# Wiegand_RS485.net
KiCad netlist of a schematic drawn in EAGLE
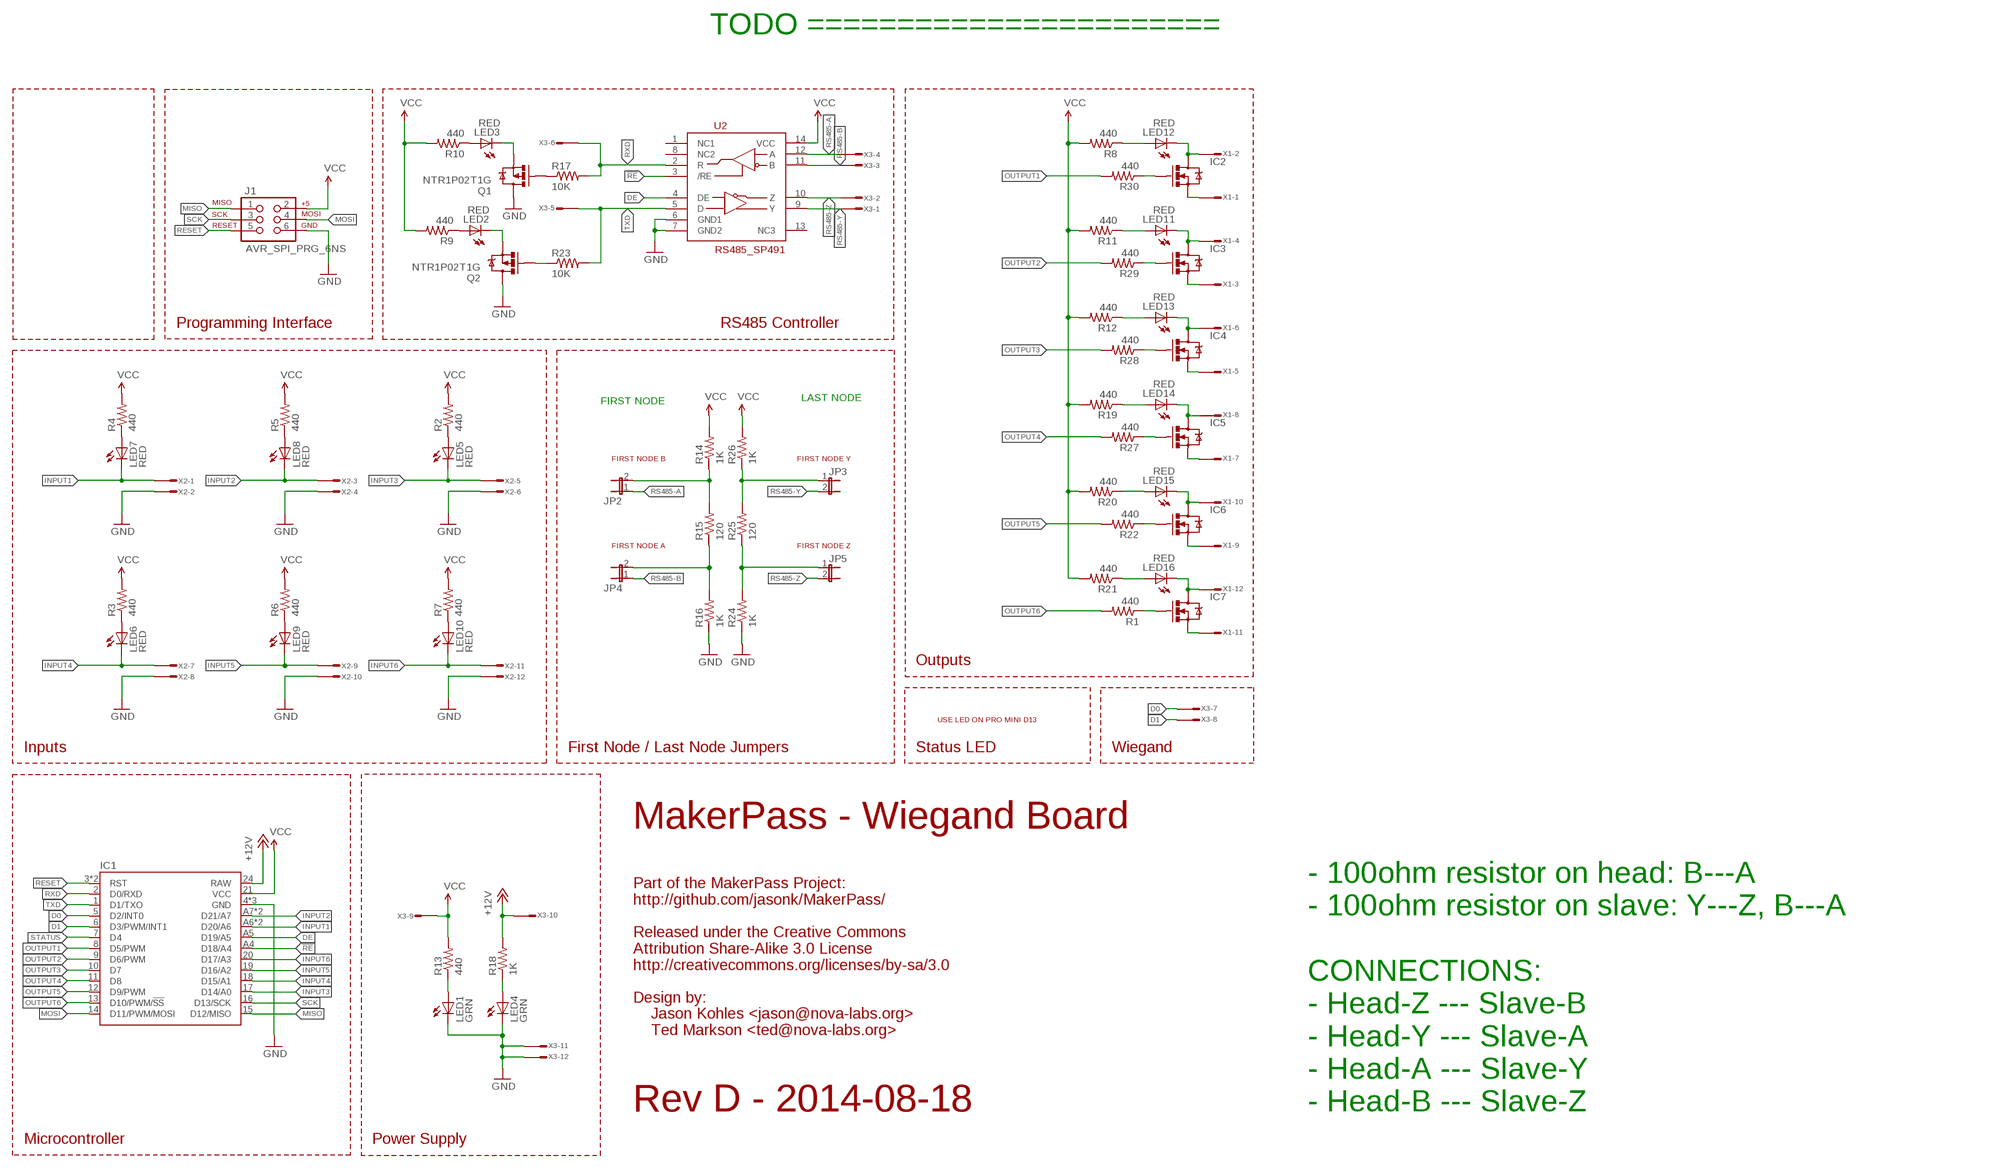
[diagram p0: schematic, sheet 1]

(export (version "E")
  (design (tool "Eeschema 10.0.6"))
  (components
    (comp (ref "IC1")
      (value "ARDUINO-PRO-MINI-ALIEXPRESS")
      (footprint "eagle-import:ARDUINO-PRO-MINI-ALIEXPRESS")
      (libsource (lib "eagle-import") (part "ARDUINO-PRO-MINI-ALIEXPRESS"))
    )
    (comp (ref "IC2")
      (value "MOSFET-NCHANNEL-SOT23")
      (footprint "eagle-import:SOT23")
      (fields (field (name "MFG") "DIODES INC"))
      (libsource (lib "eagle-import") (part "MOSFET-NCHANNEL-SOT23"))
    )
    (comp (ref "IC3")
      (value "MOSFET-NCHANNEL-SOT23")
      (footprint "eagle-import:SOT23")
      (fields (field (name "MFG") "DIODES INC"))
      (libsource (lib "eagle-import") (part "MOSFET-NCHANNEL-SOT23"))
    )
    (comp (ref "IC4")
      (value "MOSFET-NCHANNEL-SOT23")
      (footprint "eagle-import:SOT23")
      (fields (field (name "MFG") "DIODES INC"))
      (libsource (lib "eagle-import") (part "MOSFET-NCHANNEL-SOT23"))
    )
    (comp (ref "IC5")
      (value "MOSFET-NCHANNEL-SOT23")
      (footprint "eagle-import:SOT23")
      (fields (field (name "MFG") "DIODES INC"))
      (libsource (lib "eagle-import") (part "MOSFET-NCHANNEL-SOT23"))
    )
    (comp (ref "IC6")
      (value "MOSFET-NCHANNEL-SOT23")
      (footprint "eagle-import:SOT23")
      (fields (field (name "MFG") "DIODES INC"))
      (libsource (lib "eagle-import") (part "MOSFET-NCHANNEL-SOT23"))
    )
    (comp (ref "IC7")
      (value "MOSFET-NCHANNEL-SOT23")
      (footprint "eagle-import:SOT23")
      (fields (field (name "MFG") "DIODES INC"))
      (libsource (lib "eagle-import") (part "MOSFET-NCHANNEL-SOT23"))
    )
    (comp (ref "J1")
      (value "AVR_SPI_PRG_6NS")
      (footprint "eagle-import:2X3-NS")
      (libsource (lib "eagle-import") (part "AVR_SPI_PRG_6NS"))
    )
    (comp (ref "JP2")
      (value "JUMPER-2PTH")
      (footprint "eagle-import:1X02")
      (libsource (lib "eagle-import") (part "JUMPER-2PTH"))
    )
    (comp (ref "JP3")
      (value "JUMPER-2PTH")
      (footprint "eagle-import:1X02")
      (libsource (lib "eagle-import") (part "JUMPER-2PTH"))
    )
    (comp (ref "JP4")
      (value "JUMPER-2PTH")
      (footprint "eagle-import:1X02")
      (libsource (lib "eagle-import") (part "JUMPER-2PTH"))
    )
    (comp (ref "JP5")
      (value "JUMPER-2PTH")
      (footprint "eagle-import:1X02")
      (libsource (lib "eagle-import") (part "JUMPER-2PTH"))
    )
    (comp (ref "LED1")
      (value "GRN")
      (footprint "eagle-import:LED-805")
      (libsource (lib "eagle-import") (part "LED-0805"))
    )
    (comp (ref "LED2")
      (value "RED")
      (footprint "eagle-import:LED-805")
      (libsource (lib "eagle-import") (part "LED-0805"))
    )
    (comp (ref "LED3")
      (value "RED")
      (footprint "eagle-import:LED-805")
      (libsource (lib "eagle-import") (part "LED-0805"))
    )
    (comp (ref "LED4")
      (value "GRN")
      (footprint "eagle-import:LED-805")
      (libsource (lib "eagle-import") (part "LED-0805"))
    )
    (comp (ref "LED5")
      (value "RED")
      (footprint "eagle-import:LED-805")
      (libsource (lib "eagle-import") (part "LED-0805"))
    )
    (comp (ref "LED6")
      (value "RED")
      (footprint "eagle-import:LED-805")
      (libsource (lib "eagle-import") (part "LED-0805"))
    )
    (comp (ref "LED7")
      (value "RED")
      (footprint "eagle-import:LED-805")
      (libsource (lib "eagle-import") (part "LED-0805"))
    )
    (comp (ref "LED8")
      (value "RED")
      (footprint "eagle-import:LED-805")
      (libsource (lib "eagle-import") (part "LED-0805"))
    )
    (comp (ref "LED9")
      (value "RED")
      (footprint "eagle-import:LED-805")
      (libsource (lib "eagle-import") (part "LED-0805"))
    )
    (comp (ref "LED10")
      (value "RED")
      (footprint "eagle-import:LED-805")
      (libsource (lib "eagle-import") (part "LED-0805"))
    )
    (comp (ref "LED11")
      (value "RED")
      (footprint "eagle-import:LED-805")
      (libsource (lib "eagle-import") (part "LED-0805"))
    )
    (comp (ref "LED12")
      (value "RED")
      (footprint "eagle-import:LED-805")
      (libsource (lib "eagle-import") (part "LED-0805"))
    )
    (comp (ref "LED13")
      (value "RED")
      (footprint "eagle-import:LED-805")
      (libsource (lib "eagle-import") (part "LED-0805"))
    )
    (comp (ref "LED14")
      (value "RED")
      (footprint "eagle-import:LED-805")
      (libsource (lib "eagle-import") (part "LED-0805"))
    )
    (comp (ref "LED15")
      (value "RED")
      (footprint "eagle-import:LED-805")
      (libsource (lib "eagle-import") (part "LED-0805"))
    )
    (comp (ref "LED16")
      (value "RED")
      (footprint "eagle-import:LED-805")
      (libsource (lib "eagle-import") (part "LED-0805"))
    )
    (comp (ref "Q1")
      (value "NTR1P02T1G")
      (footprint "eagle-import:SOT23-3")
      (libsource (lib "eagle-import") (part "MOSFET-PCHANNELSMD"))
    )
    (comp (ref "Q2")
      (value "NTR1P02T1G")
      (footprint "eagle-import:SOT23-3")
      (libsource (lib "eagle-import") (part "MOSFET-PCHANNELSMD"))
    )
    (comp (ref "R1")
      (value "440")
      (footprint "eagle-import:0603-RES")
      (libsource (lib "eagle-import") (part "RESISTOR0603-RES"))
    )
    (comp (ref "R2")
      (value "440")
      (footprint "eagle-import:0603-RES")
      (libsource (lib "eagle-import") (part "RESISTOR0603-RES"))
    )
    (comp (ref "R3")
      (value "440")
      (footprint "eagle-import:0603-RES")
      (libsource (lib "eagle-import") (part "RESISTOR0603-RES"))
    )
    (comp (ref "R4")
      (value "440")
      (footprint "eagle-import:0603-RES")
      (libsource (lib "eagle-import") (part "RESISTOR0603-RES"))
    )
    (comp (ref "R5")
      (value "440")
      (footprint "eagle-import:0603-RES")
      (libsource (lib "eagle-import") (part "RESISTOR0603-RES"))
    )
    (comp (ref "R6")
      (value "440")
      (footprint "eagle-import:0603-RES")
      (libsource (lib "eagle-import") (part "RESISTOR0603-RES"))
    )
    (comp (ref "R7")
      (value "440")
      (footprint "eagle-import:0603-RES")
      (libsource (lib "eagle-import") (part "RESISTOR0603-RES"))
    )
    (comp (ref "R8")
      (value "440")
      (footprint "eagle-import:0603-RES")
      (libsource (lib "eagle-import") (part "RESISTOR0603-RES"))
    )
    (comp (ref "R9")
      (value "440")
      (footprint "eagle-import:0603-RES")
      (libsource (lib "eagle-import") (part "RESISTOR0603-RES"))
    )
    (comp (ref "R10")
      (value "440")
      (footprint "eagle-import:0603-RES")
      (libsource (lib "eagle-import") (part "RESISTOR0603-RES"))
    )
    (comp (ref "R11")
      (value "440")
      (footprint "eagle-import:0603-RES")
      (libsource (lib "eagle-import") (part "RESISTOR0603-RES"))
    )
    (comp (ref "R12")
      (value "440")
      (footprint "eagle-import:0603-RES")
      (libsource (lib "eagle-import") (part "RESISTOR0603-RES"))
    )
    (comp (ref "R13")
      (value "440")
      (footprint "eagle-import:0603-RES")
      (libsource (lib "eagle-import") (part "RESISTOR0603-RES"))
    )
    (comp (ref "R14")
      (value "1K")
      (footprint "eagle-import:0603-RES")
      (libsource (lib "eagle-import") (part "RESISTOR0603-RES"))
    )
    (comp (ref "R15")
      (value "120")
      (footprint "eagle-import:0603-RES")
      (libsource (lib "eagle-import") (part "RESISTOR0603-RES"))
    )
    (comp (ref "R16")
      (value "1K")
      (footprint "eagle-import:0603-RES")
      (libsource (lib "eagle-import") (part "RESISTOR0603-RES"))
    )
    (comp (ref "R17")
      (value "10K")
      (footprint "eagle-import:0603-RES")
      (libsource (lib "eagle-import") (part "RESISTOR0603-RES"))
    )
    (comp (ref "R18")
      (value "1K")
      (footprint "eagle-import:0603-RES")
      (libsource (lib "eagle-import") (part "RESISTOR0603-RES"))
    )
    (comp (ref "R19")
      (value "440")
      (footprint "eagle-import:0603-RES")
      (libsource (lib "eagle-import") (part "RESISTOR0603-RES"))
    )
    (comp (ref "R20")
      (value "440")
      (footprint "eagle-import:0603-RES")
      (libsource (lib "eagle-import") (part "RESISTOR0603-RES"))
    )
    (comp (ref "R21")
      (value "440")
      (footprint "eagle-import:0603-RES")
      (libsource (lib "eagle-import") (part "RESISTOR0603-RES"))
    )
    (comp (ref "R22")
      (value "440")
      (footprint "eagle-import:0603-RES")
      (libsource (lib "eagle-import") (part "RESISTOR0603-RES"))
    )
    (comp (ref "R23")
      (value "10K")
      (footprint "eagle-import:0603-RES")
      (libsource (lib "eagle-import") (part "RESISTOR0603-RES"))
    )
    (comp (ref "R24")
      (value "1K")
      (footprint "eagle-import:0603-RES")
      (libsource (lib "eagle-import") (part "RESISTOR0603-RES"))
    )
    (comp (ref "R25")
      (value "120")
      (footprint "eagle-import:0603-RES")
      (libsource (lib "eagle-import") (part "RESISTOR0603-RES"))
    )
    (comp (ref "R26")
      (value "1K")
      (footprint "eagle-import:0603-RES")
      (libsource (lib "eagle-import") (part "RESISTOR0603-RES"))
    )
    (comp (ref "R27")
      (value "440")
      (footprint "eagle-import:0603-RES")
      (libsource (lib "eagle-import") (part "RESISTOR0603-RES"))
    )
    (comp (ref "R28")
      (value "440")
      (footprint "eagle-import:0603-RES")
      (libsource (lib "eagle-import") (part "RESISTOR0603-RES"))
    )
    (comp (ref "R29")
      (value "440")
      (footprint "eagle-import:0603-RES")
      (libsource (lib "eagle-import") (part "RESISTOR0603-RES"))
    )
    (comp (ref "R30")
      (value "440")
      (footprint "eagle-import:0603-RES")
      (libsource (lib "eagle-import") (part "RESISTOR0603-RES"))
    )
    (comp (ref "U2")
      (value "RS485_SP491")
      (footprint "eagle-import:SOIC-14")
      (libsource (lib "eagle-import") (part "RS485_SP491"))
    )
    (comp (ref "X1")
      (value "CON-1X12-TERMBLOCK-3.5MM")
      (footprint "eagle-import:CON-1X12-TERMBLOCK-3.5MM")
      (libsource (lib "eagle-import") (part "CON-1X12-TERMBLOCK-3.5MM"))
    )
    (comp (ref "X2")
      (value "CON-1X12-TERMBLOCK-3.5MM")
      (footprint "eagle-import:CON-1X12-TERMBLOCK-3.5MM")
      (libsource (lib "eagle-import") (part "CON-1X12-TERMBLOCK-3.5MM"))
    )
    (comp (ref "X3")
      (value "CON-1X12-TERMBLOCK-3.5MM")
      (footprint "eagle-import:CON-1X12-TERMBLOCK-3.5MM")
      (libsource (lib "eagle-import") (part "CON-1X12-TERMBLOCK-3.5MM"))
    )
  )
  (nets
    (net (code "1") (name "+12V") (class "Default")
      (node (ref "IC1") (pin "24") (pinfunction "RAW_24") (pintype "power_in"))
      (node (ref "R18") (pin "2") (pinfunction "2_2") (pintype "passive"))
      (node (ref "X3") (pin "10") (pinfunction "S_10") (pintype "passive"))
    )
    (net (code "2") (name "/~{RE}") (class "Default")
      (node (ref "IC1") (pin "A4") (pinfunction "D18/A4_A4") (pintype "bidirectional"))
      (node (ref "U2") (pin "3") (pinfunction "/RE_3") (pintype "bidirectional"))
    )
    (net (code "3") (name "D0") (class "Default")
      (node (ref "IC1") (pin "5") (pinfunction "D2/INT0_5") (pintype "bidirectional"))
      (node (ref "X3") (pin "7") (pinfunction "S_7") (pintype "passive"))
    )
    (net (code "4") (name "D1") (class "Default")
      (node (ref "IC1") (pin "6") (pinfunction "D3/PWM/INT1_6") (pintype "bidirectional"))
      (node (ref "X3") (pin "8") (pinfunction "S_8") (pintype "passive"))
    )
    (net (code "5") (name "DE") (class "Default")
      (node (ref "IC1") (pin "A5") (pinfunction "D19/A5_A5") (pintype "bidirectional"))
      (node (ref "U2") (pin "4") (pinfunction "DE_4") (pintype "bidirectional"))
    )
    (net (code "6") (name "GND") (class "Default")
      (node (ref "IC1") (pin "23") (pinfunction "GND_23") (pintype "power_in"))
      (node (ref "IC1") (pin "25") (pinfunction "GND_25") (pintype "power_in"))
      (node (ref "IC1") (pin "4") (pinfunction "GND_4") (pintype "power_in"))
      (node (ref "J1") (pin "6") (pinfunction "6_6") (pintype "passive"))
      (node (ref "LED1") (pin "C") (pinfunction "C_C") (pintype "passive"))
      (node (ref "LED4") (pin "C") (pinfunction "C_C") (pintype "passive"))
      (node (ref "Q1") (pin "3") (pinfunction "D_3") (pintype "passive"))
      (node (ref "Q2") (pin "3") (pinfunction "D_3") (pintype "passive"))
      (node (ref "R16") (pin "1") (pinfunction "1_1") (pintype "passive"))
      (node (ref "R24") (pin "1") (pinfunction "1_1") (pintype "passive"))
      (node (ref "U2") (pin "6") (pinfunction "GND1_6") (pintype "bidirectional"))
      (node (ref "U2") (pin "7") (pinfunction "GND2_7") (pintype "bidirectional"))
      (node (ref "X2") (pin "10") (pinfunction "S_10") (pintype "passive"))
      (node (ref "X2") (pin "12") (pinfunction "S_12") (pintype "passive"))
      (node (ref "X2") (pin "2") (pinfunction "S_2") (pintype "passive"))
      (node (ref "X2") (pin "4") (pinfunction "S_4") (pintype "passive"))
      (node (ref "X2") (pin "6") (pinfunction "S_6") (pintype "passive"))
      (node (ref "X2") (pin "8") (pinfunction "S_8") (pintype "passive"))
      (node (ref "X3") (pin "11") (pinfunction "S_11") (pintype "passive"))
      (node (ref "X3") (pin "12") (pinfunction "S_12") (pintype "passive"))
    )
    (net (code "7") (name "INPUT1") (class "Default")
      (node (ref "IC1") (pin "A6") (pinfunction "D20/A6_A6") (pintype "bidirectional"))
      (node (ref "IC1") (pin "A6@2") (pinfunction "D20/A6_A6@2") (pintype "bidirectional"))
      (node (ref "LED7") (pin "C") (pinfunction "C_C") (pintype "passive"))
      (node (ref "X2") (pin "1") (pinfunction "S_1") (pintype "passive"))
    )
    (net (code "8") (name "INPUT2") (class "Default")
      (node (ref "IC1") (pin "A7") (pinfunction "D21/A7_A7") (pintype "bidirectional"))
      (node (ref "IC1") (pin "A7@2") (pinfunction "D21/A7_A7@2") (pintype "bidirectional"))
      (node (ref "LED8") (pin "C") (pinfunction "C_C") (pintype "passive"))
      (node (ref "X2") (pin "3") (pinfunction "S_3") (pintype "passive"))
    )
    (net (code "9") (name "INPUT3") (class "Default")
      (node (ref "IC1") (pin "17") (pinfunction "D14/A0_17") (pintype "bidirectional"))
      (node (ref "LED5") (pin "C") (pinfunction "C_C") (pintype "passive"))
      (node (ref "X2") (pin "5") (pinfunction "S_5") (pintype "passive"))
    )
    (net (code "10") (name "INPUT4") (class "Default")
      (node (ref "IC1") (pin "18") (pinfunction "D15/A1_18") (pintype "bidirectional"))
      (node (ref "LED6") (pin "C") (pinfunction "C_C") (pintype "passive"))
      (node (ref "X2") (pin "7") (pinfunction "S_7") (pintype "passive"))
    )
    (net (code "11") (name "INPUT5") (class "Default")
      (node (ref "IC1") (pin "19") (pinfunction "D16/A2_19") (pintype "bidirectional"))
      (node (ref "LED9") (pin "C") (pinfunction "C_C") (pintype "passive"))
      (node (ref "X2") (pin "9") (pinfunction "S_9") (pintype "passive"))
    )
    (net (code "12") (name "INPUT6") (class "Default")
      (node (ref "IC1") (pin "20") (pinfunction "D17/A3_20") (pintype "bidirectional"))
      (node (ref "LED10") (pin "C") (pinfunction "C_C") (pintype "passive"))
      (node (ref "X2") (pin "11") (pinfunction "S_11") (pintype "passive"))
    )
    (net (code "13") (name "MISO") (class "Default")
      (node (ref "IC1") (pin "15") (pinfunction "D12/MISO_15") (pintype "bidirectional"))
      (node (ref "J1") (pin "1") (pinfunction "1_1") (pintype "passive"))
    )
    (net (code "14") (name "MOSI") (class "Default")
      (node (ref "IC1") (pin "14") (pinfunction "D11/PWM/MOSI_14") (pintype "bidirectional"))
      (node (ref "J1") (pin "4") (pinfunction "4_4") (pintype "passive"))
    )
    (net (code "15") (name "Net-(IC2-D)") (class "Default")
      (node (ref "IC2") (pin "3") (pinfunction "D_3") (pintype "passive"))
      (node (ref "LED12") (pin "C") (pinfunction "C_C") (pintype "passive"))
      (node (ref "X1") (pin "2") (pinfunction "S_2") (pintype "passive"))
    )
    (net (code "16") (name "Net-(IC2-G)") (class "Default")
      (node (ref "IC2") (pin "1") (pinfunction "G_1") (pintype "passive"))
      (node (ref "R30") (pin "1") (pinfunction "1_1") (pintype "passive"))
    )
    (net (code "17") (name "Net-(IC2-S)") (class "Default")
      (node (ref "IC2") (pin "2") (pinfunction "S_2") (pintype "passive"))
      (node (ref "X1") (pin "1") (pinfunction "S_1") (pintype "passive"))
    )
    (net (code "18") (name "Net-(IC3-D)") (class "Default")
      (node (ref "IC3") (pin "3") (pinfunction "D_3") (pintype "passive"))
      (node (ref "LED11") (pin "C") (pinfunction "C_C") (pintype "passive"))
      (node (ref "X1") (pin "4") (pinfunction "S_4") (pintype "passive"))
    )
    (net (code "19") (name "Net-(IC3-G)") (class "Default")
      (node (ref "IC3") (pin "1") (pinfunction "G_1") (pintype "passive"))
      (node (ref "R29") (pin "1") (pinfunction "1_1") (pintype "passive"))
    )
    (net (code "20") (name "Net-(IC3-S)") (class "Default")
      (node (ref "IC3") (pin "2") (pinfunction "S_2") (pintype "passive"))
      (node (ref "X1") (pin "3") (pinfunction "S_3") (pintype "passive"))
    )
    (net (code "21") (name "Net-(IC4-D)") (class "Default")
      (node (ref "IC4") (pin "3") (pinfunction "D_3") (pintype "passive"))
      (node (ref "LED13") (pin "C") (pinfunction "C_C") (pintype "passive"))
      (node (ref "X1") (pin "6") (pinfunction "S_6") (pintype "passive"))
    )
    (net (code "22") (name "Net-(IC4-G)") (class "Default")
      (node (ref "IC4") (pin "1") (pinfunction "G_1") (pintype "passive"))
      (node (ref "R28") (pin "1") (pinfunction "1_1") (pintype "passive"))
    )
    (net (code "23") (name "Net-(IC4-S)") (class "Default")
      (node (ref "IC4") (pin "2") (pinfunction "S_2") (pintype "passive"))
      (node (ref "X1") (pin "5") (pinfunction "S_5") (pintype "passive"))
    )
    (net (code "24") (name "Net-(IC5-D)") (class "Default")
      (node (ref "IC5") (pin "3") (pinfunction "D_3") (pintype "passive"))
      (node (ref "LED14") (pin "C") (pinfunction "C_C") (pintype "passive"))
      (node (ref "X1") (pin "8") (pinfunction "S_8") (pintype "passive"))
    )
    (net (code "25") (name "Net-(IC5-G)") (class "Default")
      (node (ref "IC5") (pin "1") (pinfunction "G_1") (pintype "passive"))
      (node (ref "R27") (pin "1") (pinfunction "1_1") (pintype "passive"))
    )
    (net (code "26") (name "Net-(IC5-S)") (class "Default")
      (node (ref "IC5") (pin "2") (pinfunction "S_2") (pintype "passive"))
      (node (ref "X1") (pin "7") (pinfunction "S_7") (pintype "passive"))
    )
    (net (code "27") (name "Net-(IC6-D)") (class "Default")
      (node (ref "IC6") (pin "3") (pinfunction "D_3") (pintype "passive"))
      (node (ref "LED15") (pin "C") (pinfunction "C_C") (pintype "passive"))
      (node (ref "X1") (pin "10") (pinfunction "S_10") (pintype "passive"))
    )
    (net (code "28") (name "Net-(IC6-G)") (class "Default")
      (node (ref "IC6") (pin "1") (pinfunction "G_1") (pintype "passive"))
      (node (ref "R22") (pin "1") (pinfunction "1_1") (pintype "passive"))
    )
    (net (code "29") (name "Net-(IC6-S)") (class "Default")
      (node (ref "IC6") (pin "2") (pinfunction "S_2") (pintype "passive"))
      (node (ref "X1") (pin "9") (pinfunction "S_9") (pintype "passive"))
    )
    (net (code "30") (name "Net-(IC7-D)") (class "Default")
      (node (ref "IC7") (pin "3") (pinfunction "D_3") (pintype "passive"))
      (node (ref "LED16") (pin "C") (pinfunction "C_C") (pintype "passive"))
      (node (ref "X1") (pin "12") (pinfunction "S_12") (pintype "passive"))
    )
    (net (code "31") (name "Net-(IC7-G)") (class "Default")
      (node (ref "IC7") (pin "1") (pinfunction "G_1") (pintype "passive"))
      (node (ref "R1") (pin "1") (pinfunction "1_1") (pintype "passive"))
    )
    (net (code "32") (name "Net-(IC7-S)") (class "Default")
      (node (ref "IC7") (pin "2") (pinfunction "S_2") (pintype "passive"))
      (node (ref "X1") (pin "11") (pinfunction "S_11") (pintype "passive"))
    )
    (net (code "33") (name "Net-(JP2-Pad2)") (class "Default")
      (node (ref "JP2") (pin "2") (pinfunction "2_2") (pintype "passive"))
      (node (ref "R14") (pin "1") (pinfunction "1_1") (pintype "passive"))
      (node (ref "R15") (pin "2") (pinfunction "2_2") (pintype "passive"))
    )
    (net (code "34") (name "Net-(JP3-Pad1)") (class "Default")
      (node (ref "JP3") (pin "1") (pinfunction "1_1") (pintype "passive"))
      (node (ref "R25") (pin "2") (pinfunction "2_2") (pintype "passive"))
      (node (ref "R26") (pin "1") (pinfunction "1_1") (pintype "passive"))
    )
    (net (code "35") (name "Net-(JP4-Pad2)") (class "Default")
      (node (ref "JP4") (pin "2") (pinfunction "2_2") (pintype "passive"))
      (node (ref "R15") (pin "1") (pinfunction "1_1") (pintype "passive"))
      (node (ref "R16") (pin "2") (pinfunction "2_2") (pintype "passive"))
    )
    (net (code "36") (name "Net-(JP5-Pad1)") (class "Default")
      (node (ref "JP5") (pin "1") (pinfunction "1_1") (pintype "passive"))
      (node (ref "R24") (pin "2") (pinfunction "2_2") (pintype "passive"))
      (node (ref "R25") (pin "1") (pinfunction "1_1") (pintype "passive"))
    )
    (net (code "37") (name "Net-(LED1-PadA)") (class "Default")
      (node (ref "LED1") (pin "A") (pinfunction "A_A") (pintype "passive"))
      (node (ref "R13") (pin "1") (pinfunction "1_1") (pintype "passive"))
    )
    (net (code "38") (name "Net-(LED2-PadA)") (class "Default")
      (node (ref "LED2") (pin "A") (pinfunction "A_A") (pintype "passive"))
      (node (ref "R9") (pin "1") (pinfunction "1_1") (pintype "passive"))
    )
    (net (code "39") (name "Net-(LED3-PadA)") (class "Default")
      (node (ref "LED3") (pin "A") (pinfunction "A_A") (pintype "passive"))
      (node (ref "R10") (pin "1") (pinfunction "1_1") (pintype "passive"))
    )
    (net (code "40") (name "Net-(LED4-PadA)") (class "Default")
      (node (ref "LED4") (pin "A") (pinfunction "A_A") (pintype "passive"))
      (node (ref "R18") (pin "1") (pinfunction "1_1") (pintype "passive"))
    )
    (net (code "41") (name "Net-(LED5-PadA)") (class "Default")
      (node (ref "LED5") (pin "A") (pinfunction "A_A") (pintype "passive"))
      (node (ref "R2") (pin "1") (pinfunction "1_1") (pintype "passive"))
    )
    (net (code "42") (name "Net-(LED6-PadA)") (class "Default")
      (node (ref "LED6") (pin "A") (pinfunction "A_A") (pintype "passive"))
      (node (ref "R3") (pin "1") (pinfunction "1_1") (pintype "passive"))
    )
    (net (code "43") (name "Net-(LED7-PadA)") (class "Default")
      (node (ref "LED7") (pin "A") (pinfunction "A_A") (pintype "passive"))
      (node (ref "R4") (pin "1") (pinfunction "1_1") (pintype "passive"))
    )
    (net (code "44") (name "Net-(LED8-PadA)") (class "Default")
      (node (ref "LED8") (pin "A") (pinfunction "A_A") (pintype "passive"))
      (node (ref "R5") (pin "1") (pinfunction "1_1") (pintype "passive"))
    )
    (net (code "45") (name "Net-(LED9-PadA)") (class "Default")
      (node (ref "LED9") (pin "A") (pinfunction "A_A") (pintype "passive"))
      (node (ref "R6") (pin "1") (pinfunction "1_1") (pintype "passive"))
    )
    (net (code "46") (name "Net-(LED10-PadA)") (class "Default")
      (node (ref "LED10") (pin "A") (pinfunction "A_A") (pintype "passive"))
      (node (ref "R7") (pin "1") (pinfunction "1_1") (pintype "passive"))
    )
    (net (code "47") (name "Net-(LED11-PadA)") (class "Default")
      (node (ref "LED11") (pin "A") (pinfunction "A_A") (pintype "passive"))
      (node (ref "R11") (pin "1") (pinfunction "1_1") (pintype "passive"))
    )
    (net (code "48") (name "Net-(LED12-PadA)") (class "Default")
      (node (ref "LED12") (pin "A") (pinfunction "A_A") (pintype "passive"))
      (node (ref "R8") (pin "1") (pinfunction "1_1") (pintype "passive"))
    )
    (net (code "49") (name "Net-(LED13-PadA)") (class "Default")
      (node (ref "LED13") (pin "A") (pinfunction "A_A") (pintype "passive"))
      (node (ref "R12") (pin "1") (pinfunction "1_1") (pintype "passive"))
    )
    (net (code "50") (name "Net-(LED14-PadA)") (class "Default")
      (node (ref "LED14") (pin "A") (pinfunction "A_A") (pintype "passive"))
      (node (ref "R19") (pin "1") (pinfunction "1_1") (pintype "passive"))
    )
    (net (code "51") (name "Net-(LED15-PadA)") (class "Default")
      (node (ref "LED15") (pin "A") (pinfunction "A_A") (pintype "passive"))
      (node (ref "R20") (pin "1") (pinfunction "1_1") (pintype "passive"))
    )
    (net (code "52") (name "Net-(LED16-PadA)") (class "Default")
      (node (ref "LED16") (pin "A") (pinfunction "A_A") (pintype "passive"))
      (node (ref "R21") (pin "1") (pinfunction "1_1") (pintype "passive"))
    )
    (net (code "53") (name "Net-(Q1-G)") (class "Default")
      (node (ref "Q1") (pin "1") (pinfunction "G_1") (pintype "passive"))
      (node (ref "R17") (pin "1") (pinfunction "1_1") (pintype "passive"))
    )
    (net (code "54") (name "Net-(Q1-S)") (class "Default")
      (node (ref "LED3") (pin "C") (pinfunction "C_C") (pintype "passive"))
      (node (ref "Q1") (pin "2") (pinfunction "S_2") (pintype "passive"))
    )
    (net (code "55") (name "Net-(Q2-G)") (class "Default")
      (node (ref "Q2") (pin "1") (pinfunction "G_1") (pintype "passive"))
      (node (ref "R23") (pin "1") (pinfunction "1_1") (pintype "passive"))
    )
    (net (code "56") (name "Net-(Q2-S)") (class "Default")
      (node (ref "LED2") (pin "C") (pinfunction "C_C") (pintype "passive"))
      (node (ref "Q2") (pin "2") (pinfunction "S_2") (pintype "passive"))
    )
    (net (code "57") (name "OUTPUT1") (class "Default")
      (node (ref "IC1") (pin "8") (pinfunction "D5/PWM_8") (pintype "bidirectional"))
      (node (ref "R30") (pin "2") (pinfunction "2_2") (pintype "passive"))
    )
    (net (code "58") (name "OUTPUT2") (class "Default")
      (node (ref "IC1") (pin "9") (pinfunction "D6/PWM_9") (pintype "bidirectional"))
      (node (ref "R29") (pin "2") (pinfunction "2_2") (pintype "passive"))
    )
    (net (code "59") (name "OUTPUT3") (class "Default")
      (node (ref "IC1") (pin "10") (pinfunction "D7_10") (pintype "bidirectional"))
      (node (ref "R28") (pin "2") (pinfunction "2_2") (pintype "passive"))
    )
    (net (code "60") (name "OUTPUT4") (class "Default")
      (node (ref "IC1") (pin "11") (pinfunction "D8_11") (pintype "bidirectional"))
      (node (ref "R27") (pin "2") (pinfunction "2_2") (pintype "passive"))
    )
    (net (code "61") (name "OUTPUT5") (class "Default")
      (node (ref "IC1") (pin "12") (pinfunction "D9/PWM_12") (pintype "bidirectional"))
      (node (ref "R22") (pin "2") (pinfunction "2_2") (pintype "passive"))
    )
    (net (code "62") (name "OUTPUT6") (class "Default")
      (node (ref "IC1") (pin "13") (pinfunction "D10/PWM/~{SS}_13") (pintype "bidirectional"))
      (node (ref "R1") (pin "2") (pinfunction "2_2") (pintype "passive"))
    )
    (net (code "63") (name "RESET") (class "Default")
      (node (ref "IC1") (pin "22") (pinfunction "RST_22") (pintype "input"))
      (node (ref "IC1") (pin "3") (pinfunction "RST_3") (pintype "input"))
      (node (ref "J1") (pin "5") (pinfunction "5_5") (pintype "passive"))
    )
    (net (code "64") (name "RS485-A") (class "Default")
      (node (ref "JP2") (pin "1") (pinfunction "1_1") (pintype "passive"))
      (node (ref "U2") (pin "12") (pinfunction "A_12") (pintype "bidirectional"))
      (node (ref "X3") (pin "4") (pinfunction "S_4") (pintype "passive"))
    )
    (net (code "65") (name "RS485-B") (class "Default")
      (node (ref "JP4") (pin "1") (pinfunction "1_1") (pintype "passive"))
      (node (ref "U2") (pin "11") (pinfunction "B_11") (pintype "bidirectional"))
      (node (ref "X3") (pin "3") (pinfunction "S_3") (pintype "passive"))
    )
    (net (code "66") (name "RS485-Y") (class "Default")
      (node (ref "JP3") (pin "2") (pinfunction "2_2") (pintype "passive"))
      (node (ref "U2") (pin "9") (pinfunction "Y_9") (pintype "bidirectional"))
      (node (ref "X3") (pin "1") (pinfunction "S_1") (pintype "passive"))
    )
    (net (code "67") (name "RS485-Z") (class "Default")
      (node (ref "JP5") (pin "2") (pinfunction "2_2") (pintype "passive"))
      (node (ref "U2") (pin "10") (pinfunction "Z_10") (pintype "bidirectional"))
      (node (ref "X3") (pin "2") (pinfunction "S_2") (pintype "passive"))
    )
    (net (code "68") (name "RXD") (class "Default")
      (node (ref "IC1") (pin "2") (pinfunction "D0/RXD_2") (pintype "bidirectional"))
      (node (ref "R17") (pin "2") (pinfunction "2_2") (pintype "passive"))
      (node (ref "U2") (pin "2") (pinfunction "R_2") (pintype "bidirectional"))
      (node (ref "X3") (pin "6") (pinfunction "S_6") (pintype "passive"))
    )
    (net (code "69") (name "SCK") (class "Default")
      (node (ref "IC1") (pin "16") (pinfunction "D13/SCK_16") (pintype "bidirectional"))
      (node (ref "J1") (pin "3") (pinfunction "3_3") (pintype "passive"))
    )
    (net (code "70") (name "STATUS") (class "Default")
      (node (ref "IC1") (pin "7") (pinfunction "D4_7") (pintype "bidirectional"))
    )
    (net (code "71") (name "TXD") (class "Default")
      (node (ref "IC1") (pin "1") (pinfunction "D1/TXO_1") (pintype "bidirectional"))
      (node (ref "R23") (pin "2") (pinfunction "2_2") (pintype "passive"))
      (node (ref "U2") (pin "5") (pinfunction "D_5") (pintype "bidirectional"))
      (node (ref "X3") (pin "5") (pinfunction "S_5") (pintype "passive"))
    )
    (net (code "72") (name "VCC") (class "Default")
      (node (ref "IC1") (pin "21") (pinfunction "VCC_21") (pintype "power_in"))
      (node (ref "J1") (pin "2") (pinfunction "2_2") (pintype "passive"))
      (node (ref "R10") (pin "2") (pinfunction "2_2") (pintype "passive"))
      (node (ref "R11") (pin "2") (pinfunction "2_2") (pintype "passive"))
      (node (ref "R12") (pin "2") (pinfunction "2_2") (pintype "passive"))
      (node (ref "R13") (pin "2") (pinfunction "2_2") (pintype "passive"))
      (node (ref "R14") (pin "2") (pinfunction "2_2") (pintype "passive"))
      (node (ref "R19") (pin "2") (pinfunction "2_2") (pintype "passive"))
      (node (ref "R2") (pin "2") (pinfunction "2_2") (pintype "passive"))
      (node (ref "R20") (pin "2") (pinfunction "2_2") (pintype "passive"))
      (node (ref "R21") (pin "2") (pinfunction "2_2") (pintype "passive"))
      (node (ref "R26") (pin "2") (pinfunction "2_2") (pintype "passive"))
      (node (ref "R3") (pin "2") (pinfunction "2_2") (pintype "passive"))
      (node (ref "R4") (pin "2") (pinfunction "2_2") (pintype "passive"))
      (node (ref "R5") (pin "2") (pinfunction "2_2") (pintype "passive"))
      (node (ref "R6") (pin "2") (pinfunction "2_2") (pintype "passive"))
      (node (ref "R7") (pin "2") (pinfunction "2_2") (pintype "passive"))
      (node (ref "R8") (pin "2") (pinfunction "2_2") (pintype "passive"))
      (node (ref "R9") (pin "2") (pinfunction "2_2") (pintype "passive"))
      (node (ref "U2") (pin "14") (pinfunction "VCC_14") (pintype "bidirectional"))
      (node (ref "X3") (pin "9") (pinfunction "S_9") (pintype "passive"))
    )
    (net (code "73") (name "unconnected-(U2-NC1-Pad1)") (class "Default")
      (node (ref "U2") (pin "1") (pinfunction "NC1_1") (pintype "bidirectional"))
    )
    (net (code "74") (name "unconnected-(U2-NC2-Pad8)") (class "Default")
      (node (ref "U2") (pin "8") (pinfunction "NC2_8") (pintype "bidirectional"))
    )
    (net (code "75") (name "unconnected-(U2-NC3-Pad13)") (class "Default")
      (node (ref "U2") (pin "13") (pinfunction "NC3_13") (pintype "bidirectional"))
    )
  )
)
